# taj1050.net
KiCad netlist of a schematic drawn in Altium Designer
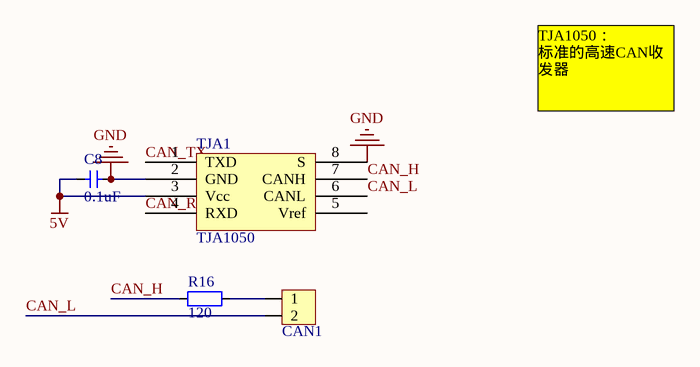
[diagram p0: taj1050.SchDoc]

(export (version "E")
  (design (tool "Eeschema 10.0.6"))
  (components
    (comp (ref "C8")
      (value "0.1uF")
      (footprint "CAP_0603")
      (description "Capacitor")
      (fields (field (name "Comment") "Cap_0603"))
      (libsource (lib "Integrated_Library") (part "Cap_0603"))
    )
    (comp (ref "CAN1")
      (value "HDR1x2_2.54")
      (footprint "HDR1X2_2.54_180")
      (description "Header")
      (libsource (lib "Integrated_Library") (part "HDR1x2_2.54"))
    )
    (comp (ref "R16")
      (value "120")
      (footprint "RES_0603")
      (description "Resistor")
      (fields (field (name "Comment") "Res_0603"))
      (libsource (lib "Integrated_Library") (part "Res_0603"))
    )
    (comp (ref "TJA1")
      (value "TJA1050")
      (footprint "SOP_E150_8")
      (description "CAN总线收发器")
      (libsource (lib "Libraries_2014_0618") (part "TJA1050"))
    )
  )
  (nets
    (net (code "1") (name "/CAN_H") (class "Default")
      (node (ref "R16") (pin "1") (pinfunction "1_1") (pintype "passive"))
      (node (ref "TJA1") (pin "7") (pinfunction "CANH_7") (pintype "passive"))
    )
    (net (code "2") (name "/CAN_L") (class "Default")
      (node (ref "CAN1") (pin "2") (pinfunction "2_2") (pintype "passive"))
      (node (ref "TJA1") (pin "6") (pinfunction "CANL_6") (pintype "passive"))
    )
    (net (code "3") (name "/CAN_RX") (class "Default")
      (node (ref "TJA1") (pin "4") (pinfunction "RXD_4") (pintype "passive"))
    )
    (net (code "4") (name "/CAN_TX") (class "Default")
      (node (ref "TJA1") (pin "1") (pinfunction "TXD_1") (pintype "passive"))
    )
    (net (code "5") (name "5V") (class "Default")
      (node (ref "C8") (pin "1") (pinfunction "1_1") (pintype "passive"))
      (node (ref "TJA1") (pin "3") (pinfunction "Vcc_3") (pintype "passive"))
    )
    (net (code "6") (name "GND") (class "Default")
      (node (ref "C8") (pin "2") (pinfunction "2_2") (pintype "passive"))
      (node (ref "TJA1") (pin "2") (pinfunction "GND_2") (pintype "passive"))
      (node (ref "TJA1") (pin "8") (pinfunction "S_8") (pintype "passive"))
    )
    (net (code "7") (name "Net-(CAN1-Pad1)") (class "Default")
      (node (ref "CAN1") (pin "1") (pinfunction "1_1") (pintype "passive"))
      (node (ref "R16") (pin "2") (pinfunction "2_2") (pintype "passive"))
    )
    (net (code "8") (name "unconnected-(TJA1-Vref-Pad5)") (class "Default")
      (node (ref "TJA1") (pin "5") (pinfunction "Vref_5") (pintype "passive"))
    )
  )
)
